# MCU.net
KiCad netlist of a schematic drawn in Altium Designer
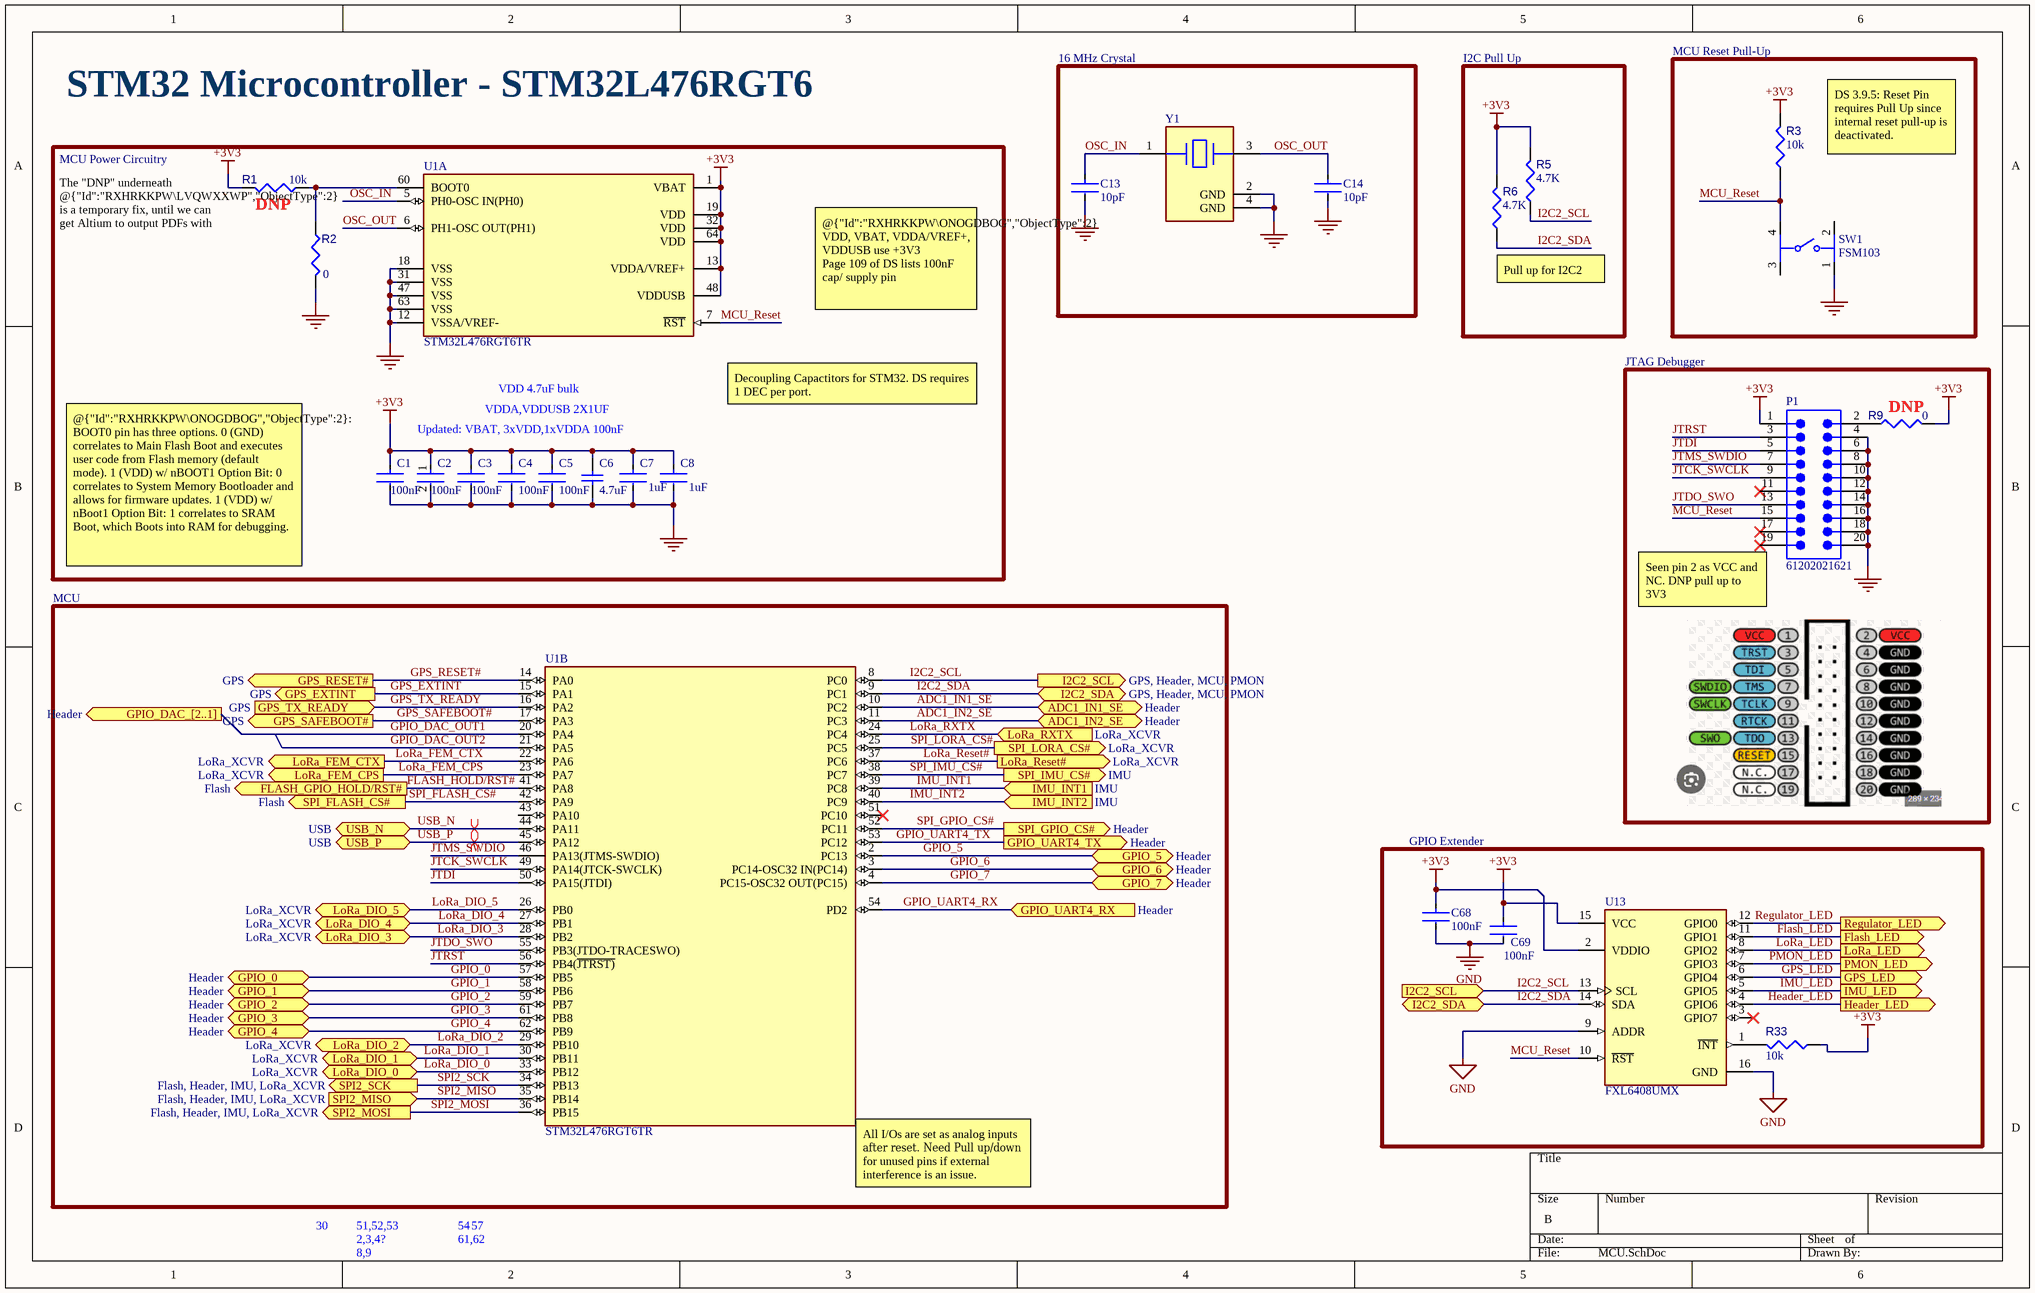
[diagram p0: MCU.SchDoc]

(export (version "E")
  (design (tool "Eeschema 10.0.6"))
  (components
    (comp (ref "C1")
      (value "100nF")
      (footprint "FP-C0402-BB-MFG")
      (description "CAP CER 0.1UF 16V X7R 0402")
      (fields
        (field (name "TOLERANCE") "0.1")
        (field (name "OCTOPART") "https://octopart.com/c0402c104k4ractu-kemet-94158")
      )
      (libsource (lib "") (part "b4654b650e69147ec39a6b967a45e02_1"))
    )
    (comp (ref "C2")
      (value "100nF")
      (footprint "FP-C0402-BB-MFG")
      (description "CAP CER 0.1UF 16V X7R 0402")
      (fields
        (field (name "TOLERANCE") "0.1")
        (field (name "OCTOPART") "https://octopart.com/c0402c104k4ractu-kemet-94158")
      )
      (libsource (lib "Altium Content Vault") (part "b4654b650e69147ec39a6b967a45e02"))
    )
    (comp (ref "C3")
      (value "100nF")
      (footprint "FP-C0402-BB-MFG")
      (description "CAP CER 0.1UF 16V X7R 0402")
      (fields
        (field (name "TOLERANCE") "0.1")
        (field (name "OCTOPART") "https://octopart.com/c0402c104k4ractu-kemet-94158")
      )
      (libsource (lib "") (part "b4654b650e69147ec39a6b967a45e02_1"))
    )
    (comp (ref "C4")
      (value "100nF")
      (footprint "FP-C0402-BB-MFG")
      (description "CAP CER 0.1UF 16V X7R 0402")
      (fields
        (field (name "TOLERANCE") "0.1")
        (field (name "OCTOPART") "https://octopart.com/c0402c104k4ractu-kemet-94158")
      )
      (libsource (lib "") (part "b4654b650e69147ec39a6b967a45e02_1"))
    )
    (comp (ref "C5")
      (value "100nF")
      (footprint "FP-C0402-BB-MFG")
      (description "CAP CER 0.1UF 16V X7R 0402")
      (fields
        (field (name "TOLERANCE") "0.1")
        (field (name "OCTOPART") "https://octopart.com/c0402c104k4ractu-kemet-94158")
      )
      (libsource (lib "") (part "b4654b650e69147ec39a6b967a45e02_1"))
    )
    (comp (ref "C6")
      (value "4.7uF")
      (footprint "CAPC2013X135X45LL10T25")
      (description "Chip Capacitor, 4.7 uF, +/- 10%, 16 V, -55 to 85 degC, 0805 (2012 Metric), RoHS, Tape and Reel")
      (fields (field (name "TOLERANCE") "10%") (field (name "PARTNUMBER") "GRM21BR61C475KA88L"))
      (libsource (lib "Altium Content Vault") (part "CAP-NP-2"))
    )
    (comp (ref "C7")
      (value "1uF")
      (footprint "FP-GRM15-MFG")
      (description "CAP CER 0.1UF 16V X7R 0402")
      (fields (field (name "MANUFACTURER PART NUMBER") "GRM155R71C104KA88D") (field (name "TOLERANCE") "10%"))
      (libsource (lib "Altium Content Vault") (part "236180d848d6139a670b325ea6854c9"))
    )
    (comp (ref "C8")
      (value "1uF")
      (footprint "FP-GRM15-MFG")
      (description "CAP CER 0.1UF 16V X7R 0402")
      (fields (field (name "MANUFACTURER PART NUMBER") "GRM155R71C104KA88D") (field (name "TOLERANCE") "10%"))
      (libsource (lib "Altium Content Vault") (part "236180d848d6139a670b325ea6854c9"))
    )
    (comp (ref "C13")
      (value "10pF")
      (footprint "FP-GRT155-0_05-MFG")
      (description "Multi-Layer Ceramic Capacitor 10pF 50V C0G ±5% 0402 Paper T/R")
      (libsource (lib "Altium Content Vault") (part "02cd4be3c70576c341d710602a673aa"))
    )
    (comp (ref "C14")
      (value "10pF")
      (footprint "FP-GRT155-0_05-MFG")
      (description "Multi-Layer Ceramic Capacitor 10pF 50V C0G ±5% 0402 Paper T/R")
      (libsource (lib "Altium Content Vault") (part "02cd4be3c70576c341d710602a673aa"))
    )
    (comp (ref "C68")
      (value "100nF")
      (footprint "FP-GRM155-0_05-IPC_B")
      (description "Chip Multilayer Ceramic Capacitors for General Purpose, 0402, 0.10uF, X7R, 15%, 10%, 50V")
      (fields (field (name "VOLTAGE") "50V") (field (name "TOLERANCE") "10%"))
      (libsource (lib "Altium Content Vault") (part "02cd4be3c70576c341d710602a673aa"))
    )
    (comp (ref "C69")
      (value "100nF")
      (footprint "FP-GRM155-0_05-IPC_B")
      (description "Chip Multilayer Ceramic Capacitors for General Purpose, 0402, 0.10uF, X7R, 15%, 10%, 50V")
      (fields (field (name "VOLTAGE") "50V") (field (name "TOLERANCE") "10%"))
      (libsource (lib "Altium Content Vault") (part "02cd4be3c70576c341d710602a673aa"))
    )
    (comp (ref "P1")
      (value "61202021621")
      (footprint "61202021621")
      (libsource (lib "Altium Content Vault") (part "Header_Male_2R_20P"))
    )
    (comp (ref "R1")
      (value "10k")
      (footprint "RESC1005X40X25ML05T05")
      (description "Chip Resistor, 10 KOhm, +/- 1%, 63 mW, -55 to 155 degC, 0402 (1005 Metric)")
      (fields (field (name "POWER") "63mW") (field (name "TOLERANCE") "1%"))
      (libsource (lib "Personal Repository") (part "RES-2"))
    )
    (comp (ref "R2")
      (value "0")
      (footprint "RESC1005X40X25ML05T05")
      (description "Chip Resistor, 10 KOhm, +/- 1%, 63 mW, -55 to 155 degC, 0402 (1005 Metric)")
      (fields (field (name "POWER") "63mW") (field (name "TOLERANCE") "1%"))
      (libsource (lib "Personal Repository") (part "RES-2"))
    )
    (comp (ref "R3")
      (value "10k")
      (footprint "RESC1005X40X25ML05T05")
      (description "Chip Resistor, 10 KOhm, +/- 1%, 0.1 W, -55 to 155 degC, 0402 (1005 Metric)")
      (fields (field (name "TOLERANCE") "1%") (field (name "POWER") "100mW"))
      (libsource (lib "Personal Repository") (part "RES-2"))
    )
    (comp (ref "R5")
      (value "4.7K")
      (footprint "RESC1005X40X25ML05T05")
      (description "Chip Resistor, 10 KOhm, +/- 1%, 0.1 W, -55 to 155 degC, 0402 (1005 Metric)")
      (fields (field (name "TOLERANCE") "1%") (field (name "POWER") "100mW"))
      (libsource (lib "Personal Repository") (part "RES-2"))
    )
    (comp (ref "R6")
      (value "4.7K")
      (footprint "RESC1005X40X25ML05T05")
      (description "Chip Resistor, 10 KOhm, +/- 1%, 0.1 W, -55 to 155 degC, 0402 (1005 Metric)")
      (fields (field (name "TOLERANCE") "1%") (field (name "POWER") "100mW"))
      (libsource (lib "Personal Repository") (part "RES-2"))
    )
    (comp (ref "R9")
      (value "0")
      (footprint "RESC1005X40X25ML05T05")
      (description "Chip Resistor, 10 KOhm, +/- 1%, 63 mW, -55 to 155 degC, 0402 (1005 Metric)")
      (fields (field (name "POWER") "63mW") (field (name "TOLERANCE") "1%"))
      (libsource (lib "Personal Repository") (part "RES-2"))
    )
    (comp (ref "R33")
      (value "10k")
      (footprint "RESC1005X40X25ML05T05")
      (description "Chip Resistor, 10 KOhm, +/- 1%, 0.1 W, -55 to 155 degC, 0402 (1005 Metric)")
      (fields (field (name "TOLERANCE") "1%") (field (name "POWER") "100mW"))
      (libsource (lib "Personal Repository") (part "RES-2"))
    )
    (comp (ref "SW1")
      (value "FSM103")
      (footprint "FP-FSM103-MFG")
      (description "SWITCH TACTILE SPST-NO 0.05A 24V")
      (libsource (lib "Altium Content Vault") (part "c0df99d12937e9d2da15afdedf14b17"))
    )
    (comp (ref "U1")
      (value "STM32L476RGT6TR")
      (footprint "FP-LQFP64-5W-MFG")
      (description "IC MCU 32BIT 1MB FLASH 64LQFP")
      (fields
        (field (name "OCTOPART") "https://octopart.com/stm32l476rgt6tr-stmicroelectronics-74146120")
        (field (name "MANUFACTURER") "STMicroelectronics")
      )
      (libsource (lib "Altium Content Vault") (part "87b63bd17e71f2d821570a63d08c5bc"))
    )
    (comp (ref "U13")
      (value "FXL6408UMX")
      (footprint "FP-523BF-MFG")
      (description "IC GPIO EXPANDER I2C 8B 16-UMLP")
      (fields
        (field (name "MANUFACTURER") "ON Semiconductor")
        (field (name "OCTOPART") "https://octopart.com/fxl6408umx-on+semiconductor-84328710")
      )
      (libsource (lib "Altium Content Vault") (part "f4b7a75440847e713e3c1dc88944eac"))
    )
    (comp (ref "Y1")
      (value "ABM3B-16.000MHZ-10-B-1-U-T")
      (footprint "FP-ABM3B-MFG")
      (description "Crystal 16MHz ±10ppm 10pF SMD-4 5mm x 3.2mm")
      (libsource (lib "Altium Content Vault") (part "48e526d86b7f2615d98721063c72f49"))
    )
  )
  (nets
    (net (code "3") (name "+3V3") (class "Default")
      (node (ref "C1") (pin "1") (pinfunction "1_1") (pintype "passive"))
      (node (ref "C2") (pin "1") (pinfunction "1_1") (pintype "passive"))
      (node (ref "C3") (pin "1") (pinfunction "1_1") (pintype "passive"))
      (node (ref "C4") (pin "1") (pinfunction "1_1") (pintype "passive"))
      (node (ref "C5") (pin "1") (pinfunction "1_1") (pintype "passive"))
      (node (ref "C6") (pin "2") (pinfunction "2_2") (pintype "passive"))
      (node (ref "C68") (pin "1") (pinfunction "1_1") (pintype "passive"))
      (node (ref "C69") (pin "1") (pinfunction "1_1") (pintype "passive"))
      (node (ref "C7") (pin "2") (pinfunction "2_2") (pintype "passive"))
      (node (ref "C8") (pin "2") (pinfunction "2_2") (pintype "passive"))
      (node (ref "P1") (pin "1") (pinfunction "1_1") (pintype "passive"))
      (node (ref "R1") (pin "2") (pinfunction "2_2") (pintype "passive"))
      (node (ref "R3") (pin "2") (pinfunction "2_2") (pintype "passive"))
      (node (ref "R33") (pin "1") (pinfunction "1_1") (pintype "passive"))
      (node (ref "R5") (pin "2") (pinfunction "2_2") (pintype "passive"))
      (node (ref "R6") (pin "2") (pinfunction "2_2") (pintype "passive"))
      (node (ref "R9") (pin "2") (pinfunction "2_2") (pintype "passive"))
      (node (ref "U1") (pin "1") (pinfunction "VBAT_1") (pintype "power_in"))
      (node (ref "U1") (pin "13") (pinfunction "VDDA/VREF+_13") (pintype "power_in"))
      (node (ref "U1") (pin "19") (pinfunction "VDD_19") (pintype "power_in"))
      (node (ref "U1") (pin "32") (pinfunction "VDD_32") (pintype "power_in"))
      (node (ref "U1") (pin "48") (pinfunction "VDDUSB_48") (pintype "power_in"))
      (node (ref "U1") (pin "64") (pinfunction "VDD_64") (pintype "power_in"))
      (node (ref "U13") (pin "15") (pinfunction "VCC_15") (pintype "power_in"))
      (node (ref "U13") (pin "2") (pinfunction "VDDIO_2") (pintype "power_in"))
    )
    (net (code "4") (name "/ADC1_IN1_SE") (class "Default")
      (node (ref "U1") (pin "10") (pinfunction "PC2_10") (pintype "bidirectional"))
    )
    (net (code "5") (name "/ADC1_IN2_SE") (class "Default")
      (node (ref "U1") (pin "11") (pinfunction "PC3_11") (pintype "bidirectional"))
    )
    (net (code "6") (name "/FLASH_HOLD{slash}RST#") (class "Default")
      (node (ref "U1") (pin "41") (pinfunction "PA8_41") (pintype "bidirectional"))
    )
    (net (code "7") (name "/Flash_LED") (class "Default")
      (node (ref "U13") (pin "11") (pinfunction "GPIO1_11") (pintype "bidirectional"))
    )
    (net (code "8") (name "/GPIO_0") (class "Default")
      (node (ref "U1") (pin "57") (pinfunction "PB5_57") (pintype "bidirectional"))
    )
    (net (code "9") (name "/GPIO_1") (class "Default")
      (node (ref "U1") (pin "58") (pinfunction "PB6_58") (pintype "bidirectional"))
    )
    (net (code "10") (name "/GPIO_2") (class "Default")
      (node (ref "U1") (pin "59") (pinfunction "PB7_59") (pintype "bidirectional"))
    )
    (net (code "11") (name "/GPIO_3") (class "Default")
      (node (ref "U1") (pin "61") (pinfunction "PB8_61") (pintype "bidirectional"))
    )
    (net (code "12") (name "/GPIO_4") (class "Default")
      (node (ref "U1") (pin "62") (pinfunction "PB9_62") (pintype "bidirectional"))
    )
    (net (code "13") (name "/GPIO_5") (class "Default")
      (node (ref "U1") (pin "2") (pinfunction "PC13_2") (pintype "bidirectional"))
    )
    (net (code "14") (name "/GPIO_6") (class "Default")
      (node (ref "U1") (pin "3") (pinfunction "PC14-OSC32_IN(PC14)_3") (pintype "bidirectional"))
    )
    (net (code "15") (name "/GPIO_7") (class "Default")
      (node (ref "U1") (pin "4") (pinfunction "PC15-OSC32_OUT(PC15)_4") (pintype "bidirectional"))
    )
    (net (code "16") (name "/GPIO_DAC_OUT1") (class "Default")
      (node (ref "U1") (pin "20") (pinfunction "PA4_20") (pintype "bidirectional"))
    )
    (net (code "17") (name "/GPIO_DAC_OUT2") (class "Default")
      (node (ref "U1") (pin "21") (pinfunction "PA5_21") (pintype "bidirectional"))
    )
    (net (code "19") (name "/GPIO_UART4_RX") (class "Default")
      (node (ref "U1") (pin "54") (pinfunction "PD2_54") (pintype "bidirectional"))
    )
    (net (code "20") (name "/GPIO_UART4_TX") (class "Default")
      (node (ref "U1") (pin "53") (pinfunction "PC12_53") (pintype "bidirectional"))
    )
    (net (code "21") (name "/GPS_EXTINT") (class "Default")
      (node (ref "U1") (pin "15") (pinfunction "PA1_15") (pintype "bidirectional"))
    )
    (net (code "22") (name "/GPS_LED") (class "Default")
      (node (ref "U13") (pin "6") (pinfunction "GPIO4_6") (pintype "bidirectional"))
    )
    (net (code "23") (name "/GPS_RESET#") (class "Default")
      (node (ref "U1") (pin "14") (pinfunction "PA0_14") (pintype "bidirectional"))
    )
    (net (code "24") (name "/GPS_SAFEBOOT#") (class "Default")
      (node (ref "U1") (pin "17") (pinfunction "PA3_17") (pintype "bidirectional"))
    )
    (net (code "25") (name "/GPS_TX_READY") (class "Default")
      (node (ref "U1") (pin "16") (pinfunction "PA2_16") (pintype "bidirectional"))
    )
    (net (code "26") (name "/Header_LED") (class "Default")
      (node (ref "U13") (pin "4") (pinfunction "GPIO6_4") (pintype "bidirectional"))
    )
    (net (code "27") (name "/I2C2_SCL") (class "Default")
      (node (ref "R5") (pin "1") (pinfunction "1_1") (pintype "passive"))
      (node (ref "U1") (pin "8") (pinfunction "PC0_8") (pintype "bidirectional"))
      (node (ref "U13") (pin "13") (pinfunction "SCL_13") (pintype "input"))
    )
    (net (code "28") (name "/I2C2_SDA") (class "Default")
      (node (ref "R6") (pin "1") (pinfunction "1_1") (pintype "passive"))
      (node (ref "U1") (pin "9") (pinfunction "PC1_9") (pintype "bidirectional"))
      (node (ref "U13") (pin "14") (pinfunction "SDA_14") (pintype "bidirectional"))
    )
    (net (code "29") (name "/IMU_INT1") (class "Default")
      (node (ref "U1") (pin "39") (pinfunction "PC8_39") (pintype "bidirectional"))
    )
    (net (code "30") (name "/IMU_INT2") (class "Default")
      (node (ref "U1") (pin "40") (pinfunction "PC9_40") (pintype "bidirectional"))
    )
    (net (code "31") (name "/IMU_LED") (class "Default")
      (node (ref "U13") (pin "5") (pinfunction "GPIO5_5") (pintype "bidirectional"))
    )
    (net (code "32") (name "/JTCK_SWCLK") (class "Default")
      (node (ref "P1") (pin "9") (pinfunction "9_9") (pintype "passive"))
      (node (ref "U1") (pin "49") (pinfunction "PA14(JTCK-SWCLK)_49") (pintype "bidirectional"))
    )
    (net (code "33") (name "/JTDI") (class "Default")
      (node (ref "P1") (pin "5") (pinfunction "5_5") (pintype "passive"))
      (node (ref "U1") (pin "50") (pinfunction "PA15(JTDI)_50") (pintype "bidirectional"))
    )
    (net (code "34") (name "/JTDO_SWO") (class "Default")
      (node (ref "P1") (pin "13") (pinfunction "13_13") (pintype "passive"))
      (node (ref "U1") (pin "55") (pinfunction "PB3(JTDO-TRACESWO)_55") (pintype "bidirectional"))
    )
    (net (code "35") (name "/JTMS_SWDIO") (class "Default")
      (node (ref "P1") (pin "7") (pinfunction "7_7") (pintype "passive"))
      (node (ref "U1") (pin "46") (pinfunction "PA13(JTMS-SWDIO)_46") (pintype "power_in"))
    )
    (net (code "36") (name "/JTRST") (class "Default")
      (node (ref "P1") (pin "3") (pinfunction "3_3") (pintype "passive"))
      (node (ref "U1") (pin "56") (pinfunction "PB4(~{JTRST)}_56") (pintype "bidirectional"))
    )
    (net (code "37") (name "/LoRa_DIO_0") (class "Default")
      (node (ref "U1") (pin "33") (pinfunction "PB12_33") (pintype "bidirectional"))
    )
    (net (code "38") (name "/LoRa_DIO_1") (class "Default")
      (node (ref "U1") (pin "30") (pinfunction "PB11_30") (pintype "bidirectional"))
    )
    (net (code "39") (name "/LoRa_DIO_2") (class "Default")
      (node (ref "U1") (pin "29") (pinfunction "PB10_29") (pintype "bidirectional"))
    )
    (net (code "40") (name "/LoRa_DIO_3") (class "Default")
      (node (ref "U1") (pin "28") (pinfunction "PB2_28") (pintype "bidirectional"))
    )
    (net (code "41") (name "/LoRa_DIO_4") (class "Default")
      (node (ref "U1") (pin "27") (pinfunction "PB1_27") (pintype "bidirectional"))
    )
    (net (code "42") (name "/LoRa_DIO_5") (class "Default")
      (node (ref "U1") (pin "26") (pinfunction "PB0_26") (pintype "bidirectional"))
    )
    (net (code "43") (name "/LoRa_FEM_CPS") (class "Default")
      (node (ref "U1") (pin "23") (pinfunction "PA7_23") (pintype "bidirectional"))
    )
    (net (code "44") (name "/LoRa_FEM_CTX") (class "Default")
      (node (ref "U1") (pin "22") (pinfunction "PA6_22") (pintype "bidirectional"))
    )
    (net (code "45") (name "/LoRa_LED") (class "Default")
      (node (ref "U13") (pin "8") (pinfunction "GPIO2_8") (pintype "bidirectional"))
    )
    (net (code "46") (name "/LoRa_RXTX") (class "Default")
      (node (ref "U1") (pin "24") (pinfunction "PC4_24") (pintype "bidirectional"))
    )
    (net (code "47") (name "/LoRa_Reset#") (class "Default")
      (node (ref "U1") (pin "37") (pinfunction "PC6_37") (pintype "bidirectional"))
    )
    (net (code "48") (name "/MCU_Reset") (class "Default")
      (node (ref "P1") (pin "15") (pinfunction "15_15") (pintype "passive"))
      (node (ref "R3") (pin "1") (pinfunction "1_1") (pintype "passive"))
      (node (ref "SW1") (pin "4") (pinfunction "4_4") (pintype "passive"))
      (node (ref "U1") (pin "7") (pinfunction "~{RST}_7") (pintype "input"))
      (node (ref "U13") (pin "10") (pinfunction "~{RST}_10") (pintype "input"))
    )
    (net (code "49") (name "/OSC_IN") (class "Default")
      (node (ref "C13") (pin "1") (pinfunction "1_1") (pintype "passive"))
      (node (ref "U1") (pin "5") (pinfunction "PH0-OSC_IN(PH0)_5") (pintype "bidirectional"))
      (node (ref "Y1") (pin "1") (pinfunction "1_1") (pintype "passive"))
    )
    (net (code "50") (name "/OSC_OUT") (class "Default")
      (node (ref "C14") (pin "1") (pinfunction "1_1") (pintype "passive"))
      (node (ref "U1") (pin "6") (pinfunction "PH1-OSC_OUT(PH1)_6") (pintype "bidirectional"))
      (node (ref "Y1") (pin "3") (pinfunction "3_3") (pintype "passive"))
    )
    (net (code "51") (name "/PMON_LED") (class "Default")
      (node (ref "U13") (pin "7") (pinfunction "GPIO3_7") (pintype "bidirectional"))
    )
    (net (code "52") (name "/Regulator_LED") (class "Default")
      (node (ref "U13") (pin "12") (pinfunction "GPIO0_12") (pintype "bidirectional"))
    )
    (net (code "53") (name "/SPI2_MISO") (class "Default")
      (node (ref "U1") (pin "35") (pinfunction "PB14_35") (pintype "bidirectional"))
    )
    (net (code "54") (name "/SPI2_MOSI") (class "Default")
      (node (ref "U1") (pin "36") (pinfunction "PB15_36") (pintype "bidirectional"))
    )
    (net (code "55") (name "/SPI2_SCK") (class "Default")
      (node (ref "U1") (pin "34") (pinfunction "PB13_34") (pintype "bidirectional"))
    )
    (net (code "56") (name "/SPI_FLASH_CS#") (class "Default")
      (node (ref "U1") (pin "42") (pinfunction "PA9_42") (pintype "bidirectional"))
    )
    (net (code "57") (name "/SPI_GPIO_CS#") (class "Default")
      (node (ref "U1") (pin "52") (pinfunction "PC11_52") (pintype "bidirectional"))
    )
    (net (code "58") (name "/SPI_IMU_CS#") (class "Default")
      (node (ref "U1") (pin "38") (pinfunction "PC7_38") (pintype "bidirectional"))
    )
    (net (code "59") (name "/SPI_LORA_CS#") (class "Default")
      (node (ref "U1") (pin "25") (pinfunction "PC5_25") (pintype "bidirectional"))
    )
    (net (code "60") (name "/USB_N") (class "Default")
      (node (ref "U1") (pin "44") (pinfunction "PA11_44") (pintype "bidirectional"))
    )
    (net (code "61") (name "/USB_P") (class "Default")
      (node (ref "U1") (pin "45") (pinfunction "PA12_45") (pintype "bidirectional"))
    )
    (net (code "62") (name "GND") (class "Default")
      (node (ref "C1") (pin "2") (pinfunction "2_2") (pintype "passive"))
      (node (ref "C13") (pin "2") (pinfunction "2_2") (pintype "passive"))
      (node (ref "C14") (pin "2") (pinfunction "2_2") (pintype "passive"))
      (node (ref "C2") (pin "2") (pinfunction "2_2") (pintype "passive"))
      (node (ref "C3") (pin "2") (pinfunction "2_2") (pintype "passive"))
      (node (ref "C4") (pin "2") (pinfunction "2_2") (pintype "passive"))
      (node (ref "C5") (pin "2") (pinfunction "2_2") (pintype "passive"))
      (node (ref "C6") (pin "1") (pinfunction "1_1") (pintype "passive"))
      (node (ref "C68") (pin "2") (pinfunction "2_2") (pintype "passive"))
      (node (ref "C69") (pin "2") (pinfunction "2_2") (pintype "passive"))
      (node (ref "C7") (pin "1") (pinfunction "1_1") (pintype "passive"))
      (node (ref "C8") (pin "1") (pinfunction "1_1") (pintype "passive"))
      (node (ref "P1") (pin "10") (pinfunction "10_10") (pintype "passive"))
      (node (ref "P1") (pin "12") (pinfunction "12_12") (pintype "passive"))
      (node (ref "P1") (pin "14") (pinfunction "14_14") (pintype "passive"))
      (node (ref "P1") (pin "16") (pinfunction "16_16") (pintype "passive"))
      (node (ref "P1") (pin "18") (pinfunction "18_18") (pintype "passive"))
      (node (ref "P1") (pin "20") (pinfunction "20_20") (pintype "passive"))
      (node (ref "P1") (pin "4") (pinfunction "4_4") (pintype "passive"))
      (node (ref "P1") (pin "6") (pinfunction "6_6") (pintype "passive"))
      (node (ref "P1") (pin "8") (pinfunction "8_8") (pintype "passive"))
      (node (ref "R2") (pin "2") (pinfunction "2_2") (pintype "passive"))
      (node (ref "SW1") (pin "1") (pinfunction "1_1") (pintype "passive"))
      (node (ref "U1") (pin "12") (pinfunction "VSSA/VREF-_12") (pintype "power_in"))
      (node (ref "U1") (pin "18") (pinfunction "VSS_18") (pintype "power_in"))
      (node (ref "U1") (pin "31") (pinfunction "VSS_31") (pintype "power_in"))
      (node (ref "U1") (pin "47") (pinfunction "VSS_47") (pintype "power_in"))
      (node (ref "U1") (pin "63") (pinfunction "VSS_63") (pintype "power_in"))
      (node (ref "U13") (pin "16") (pinfunction "GND_16") (pintype "power_in"))
      (node (ref "U13") (pin "9") (pinfunction "ADDR_9") (pintype "input"))
      (node (ref "Y1") (pin "2") (pinfunction "GND_2") (pintype "power_in"))
      (node (ref "Y1") (pin "4") (pinfunction "GND_4") (pintype "power_in"))
    )
    (net (code "63") (name "Net-(P1-Pad2)") (class "Default")
      (node (ref "P1") (pin "2") (pinfunction "2_2") (pintype "passive"))
      (node (ref "R9") (pin "1") (pinfunction "1_1") (pintype "passive"))
    )
    (net (code "64") (name "Net-(U1A-BOOT0)") (class "Default")
      (node (ref "R1") (pin "1") (pinfunction "1_1") (pintype "passive"))
      (node (ref "R2") (pin "1") (pinfunction "1_1") (pintype "passive"))
      (node (ref "U1") (pin "60") (pinfunction "BOOT0_60") (pintype "passive"))
    )
    (net (code "65") (name "Net-(U13-~{INT})") (class "Default")
      (node (ref "R33") (pin "2") (pinfunction "2_2") (pintype "passive"))
      (node (ref "U13") (pin "1") (pinfunction "~{INT}_1") (pintype "output"))
    )
    (net (code "66") (name "unconnected-(P1-Pad11)") (class "Default")
      (node (ref "P1") (pin "11") (pinfunction "11_11") (pintype "passive+no_connect"))
    )
    (net (code "67") (name "unconnected-(P1-Pad17)") (class "Default")
      (node (ref "P1") (pin "17") (pinfunction "17_17") (pintype "passive+no_connect"))
    )
    (net (code "68") (name "unconnected-(P1-Pad19)") (class "Default")
      (node (ref "P1") (pin "19") (pinfunction "19_19") (pintype "passive+no_connect"))
    )
    (net (code "69") (name "unconnected-(SW1-Pad2)") (class "Default")
      (node (ref "SW1") (pin "2") (pinfunction "2_2") (pintype "passive"))
    )
    (net (code "70") (name "unconnected-(SW1-Pad3)") (class "Default")
      (node (ref "SW1") (pin "3") (pinfunction "3_3") (pintype "passive"))
    )
    (net (code "71") (name "unconnected-(U1B-PA10-Pad43)") (class "Default")
      (node (ref "U1") (pin "43") (pinfunction "PA10_43") (pintype "bidirectional"))
    )
    (net (code "72") (name "unconnected-(U1B-PC10-Pad51)") (class "Default")
      (node (ref "U1") (pin "51") (pinfunction "PC10_51") (pintype "bidirectional+no_connect"))
    )
    (net (code "73") (name "unconnected-(U13-GPIO7-Pad3)") (class "Default")
      (node (ref "U13") (pin "3") (pinfunction "GPIO7_3") (pintype "bidirectional+no_connect"))
    )
  )
)
